# scheamt_projekt.net
KiCad netlist of a schematic drawn in EAGLE
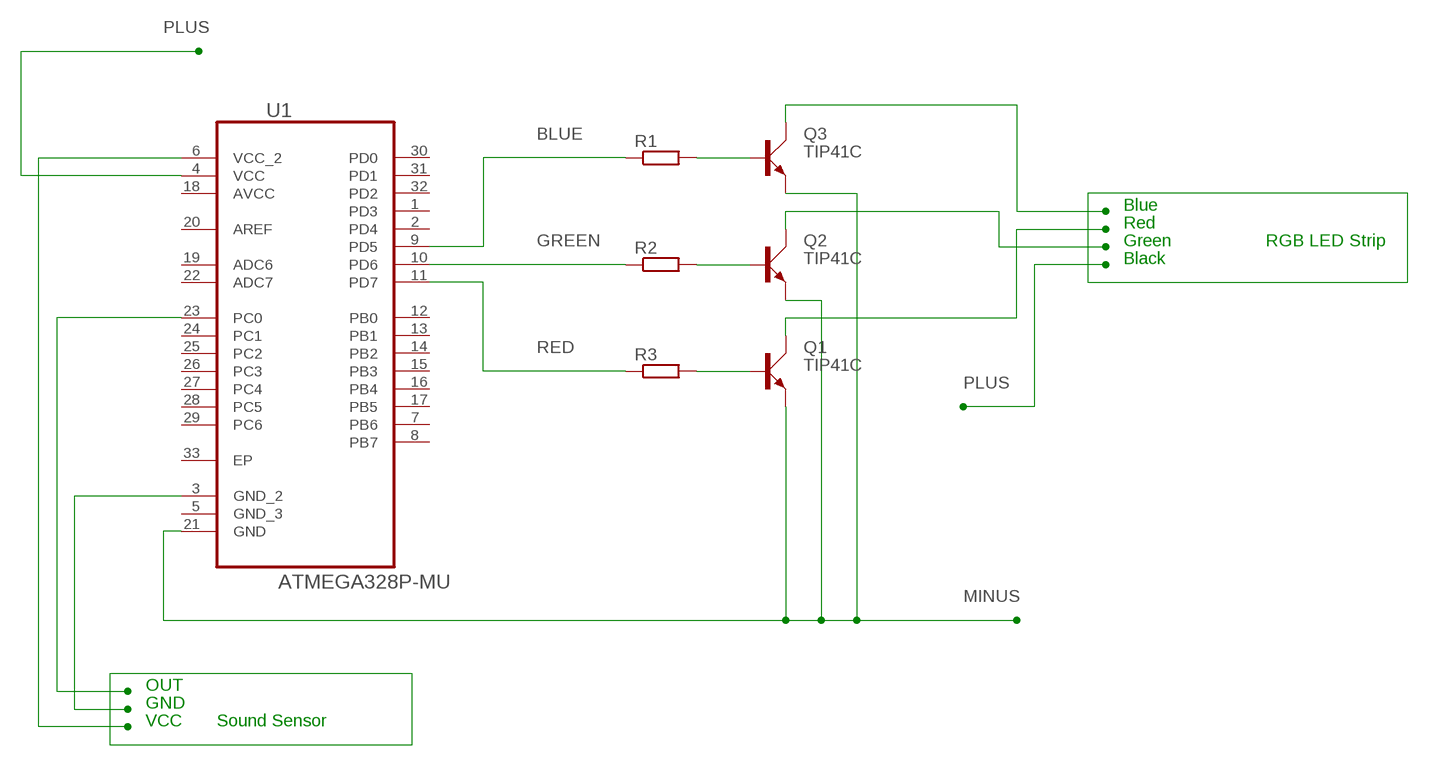
[diagram p0: schematic, sheet 1]

(export (version "E")
  (design (tool "Eeschema 10.0.6"))
  (components
    (comp (ref "Q1")
      (value "TIP41C")
      (footprint "eagle-import:TO220AV")
      (libsource (lib "eagle-import") (part "TIP41C"))
    )
    (comp (ref "Q2")
      (value "TIP41C")
      (footprint "eagle-import:TO220AV")
      (libsource (lib "eagle-import") (part "TIP41C"))
    )
    (comp (ref "Q3")
      (value "TIP41C")
      (footprint "eagle-import:TO220AV")
      (libsource (lib "eagle-import") (part "TIP41C"))
    )
    (comp (ref "R1")
      (value "R-EU_0204/7")
      (footprint "eagle-import:0204_7")
      (libsource (lib "eagle-import") (part "R-EU_0204/7"))
    )
    (comp (ref "R2")
      (value "R-EU_0204/7")
      (footprint "eagle-import:0204_7")
      (libsource (lib "eagle-import") (part "R-EU_0204/7"))
    )
    (comp (ref "R3")
      (value "R-EU_0204/7")
      (footprint "eagle-import:0204_7")
      (libsource (lib "eagle-import") (part "R-EU_0204/7"))
    )
    (comp (ref "U1")
      (value "ATMEGA328P-MU")
      (footprint "eagle-import:QFN50P500X500X100-33N")
      (fields (field (name "SUPPLIER") "Atmel"))
      (libsource (lib "eagle-import") (part "ATMEGA328P-MU"))
    )
  )
  (nets
    (net (code "1") (name "/AVCC") (class "Default")
      (node (ref "U1") (pin "18") (pinfunction "AVCC_18") (pintype "power_in"))
    )
    (net (code "2") (name "/BLUE") (class "Default")
      (node (ref "R1") (pin "1") (pinfunction "1_1") (pintype "passive"))
      (node (ref "U1") (pin "9") (pinfunction "PD5_9") (pintype "bidirectional"))
    )
    (net (code "3") (name "/GREEN") (class "Default")
      (node (ref "R2") (pin "1") (pinfunction "1_1") (pintype "passive"))
      (node (ref "U1") (pin "10") (pinfunction "PD6_10") (pintype "bidirectional"))
    )
    (net (code "4") (name "/MINUS") (class "Default")
      (node (ref "Q1") (pin "E") (pinfunction "E_E") (pintype "passive"))
      (node (ref "Q2") (pin "E") (pinfunction "E_E") (pintype "passive"))
      (node (ref "Q3") (pin "E") (pinfunction "E_E") (pintype "passive"))
      (node (ref "U1") (pin "21") (pinfunction "GND_21") (pintype "passive"))
    )
    (net (code "5") (name "/PLUS") (class "Default")
      (node (ref "U1") (pin "4") (pinfunction "VCC_4") (pintype "power_in"))
    )
    (net (code "6") (name "/RED") (class "Default")
      (node (ref "R3") (pin "1") (pinfunction "1_1") (pintype "passive"))
      (node (ref "U1") (pin "11") (pinfunction "PD7_11") (pintype "bidirectional"))
    )
    (net (code "7") (name "Net-(Q1-PadB)") (class "Default")
      (node (ref "Q1") (pin "B") (pinfunction "B_B") (pintype "passive"))
      (node (ref "R3") (pin "2") (pinfunction "2_2") (pintype "passive"))
    )
    (net (code "8") (name "Net-(Q2-PadB)") (class "Default")
      (node (ref "Q2") (pin "B") (pinfunction "B_B") (pintype "passive"))
      (node (ref "R2") (pin "2") (pinfunction "2_2") (pintype "passive"))
    )
    (net (code "9") (name "Net-(Q3-PadB)") (class "Default")
      (node (ref "Q3") (pin "B") (pinfunction "B_B") (pintype "passive"))
      (node (ref "R1") (pin "2") (pinfunction "2_2") (pintype "passive"))
    )
    (net (code "10") (name "unconnected-(Q1-PadC)") (class "Default")
      (node (ref "Q1") (pin "C") (pinfunction "C_C") (pintype "passive"))
    )
    (net (code "11") (name "unconnected-(Q2-PadC)") (class "Default")
      (node (ref "Q2") (pin "C") (pinfunction "C_C") (pintype "passive"))
    )
    (net (code "12") (name "unconnected-(Q3-PadC)") (class "Default")
      (node (ref "Q3") (pin "C") (pinfunction "C_C") (pintype "passive"))
    )
    (net (code "13") (name "unconnected-(U1-ADC6-Pad19)") (class "Default")
      (node (ref "U1") (pin "19") (pinfunction "ADC6_19") (pintype "input"))
    )
    (net (code "14") (name "unconnected-(U1-ADC7-Pad22)") (class "Default")
      (node (ref "U1") (pin "22") (pinfunction "ADC7_22") (pintype "input"))
    )
    (net (code "15") (name "unconnected-(U1-AREF-Pad20)") (class "Default")
      (node (ref "U1") (pin "20") (pinfunction "AREF_20") (pintype "input"))
    )
    (net (code "16") (name "unconnected-(U1-EP-Pad33)") (class "Default")
      (node (ref "U1") (pin "33") (pinfunction "EP_33") (pintype "passive"))
    )
    (net (code "17") (name "unconnected-(U1-GND_2-Pad3)") (class "Default")
      (node (ref "U1") (pin "3") (pinfunction "GND_2_3") (pintype "passive"))
    )
    (net (code "18") (name "unconnected-(U1-GND_3-Pad5)") (class "Default")
      (node (ref "U1") (pin "5") (pinfunction "GND_3_5") (pintype "passive"))
    )
    (net (code "19") (name "unconnected-(U1-PB0-Pad12)") (class "Default")
      (node (ref "U1") (pin "12") (pinfunction "PB0_12") (pintype "bidirectional"))
    )
    (net (code "20") (name "unconnected-(U1-PB1-Pad13)") (class "Default")
      (node (ref "U1") (pin "13") (pinfunction "PB1_13") (pintype "bidirectional"))
    )
    (net (code "21") (name "unconnected-(U1-PB2-Pad14)") (class "Default")
      (node (ref "U1") (pin "14") (pinfunction "PB2_14") (pintype "bidirectional"))
    )
    (net (code "22") (name "unconnected-(U1-PB3-Pad15)") (class "Default")
      (node (ref "U1") (pin "15") (pinfunction "PB3_15") (pintype "bidirectional"))
    )
    (net (code "23") (name "unconnected-(U1-PB4-Pad16)") (class "Default")
      (node (ref "U1") (pin "16") (pinfunction "PB4_16") (pintype "bidirectional"))
    )
    (net (code "24") (name "unconnected-(U1-PB5-Pad17)") (class "Default")
      (node (ref "U1") (pin "17") (pinfunction "PB5_17") (pintype "bidirectional"))
    )
    (net (code "25") (name "unconnected-(U1-PB6-Pad7)") (class "Default")
      (node (ref "U1") (pin "7") (pinfunction "PB6_7") (pintype "bidirectional"))
    )
    (net (code "26") (name "unconnected-(U1-PB7-Pad8)") (class "Default")
      (node (ref "U1") (pin "8") (pinfunction "PB7_8") (pintype "bidirectional"))
    )
    (net (code "27") (name "unconnected-(U1-PC0-Pad23)") (class "Default")
      (node (ref "U1") (pin "23") (pinfunction "PC0_23") (pintype "bidirectional"))
    )
    (net (code "28") (name "unconnected-(U1-PC1-Pad24)") (class "Default")
      (node (ref "U1") (pin "24") (pinfunction "PC1_24") (pintype "bidirectional"))
    )
    (net (code "29") (name "unconnected-(U1-PC2-Pad25)") (class "Default")
      (node (ref "U1") (pin "25") (pinfunction "PC2_25") (pintype "bidirectional"))
    )
    (net (code "30") (name "unconnected-(U1-PC3-Pad26)") (class "Default")
      (node (ref "U1") (pin "26") (pinfunction "PC3_26") (pintype "bidirectional"))
    )
    (net (code "31") (name "unconnected-(U1-PC4-Pad27)") (class "Default")
      (node (ref "U1") (pin "27") (pinfunction "PC4_27") (pintype "bidirectional"))
    )
    (net (code "32") (name "unconnected-(U1-PC5-Pad28)") (class "Default")
      (node (ref "U1") (pin "28") (pinfunction "PC5_28") (pintype "bidirectional"))
    )
    (net (code "33") (name "unconnected-(U1-PC6-Pad29)") (class "Default")
      (node (ref "U1") (pin "29") (pinfunction "PC6_29") (pintype "bidirectional"))
    )
    (net (code "34") (name "unconnected-(U1-PD0-Pad30)") (class "Default")
      (node (ref "U1") (pin "30") (pinfunction "PD0_30") (pintype "bidirectional"))
    )
    (net (code "35") (name "unconnected-(U1-PD1-Pad31)") (class "Default")
      (node (ref "U1") (pin "31") (pinfunction "PD1_31") (pintype "bidirectional"))
    )
    (net (code "36") (name "unconnected-(U1-PD2-Pad32)") (class "Default")
      (node (ref "U1") (pin "32") (pinfunction "PD2_32") (pintype "bidirectional"))
    )
    (net (code "37") (name "unconnected-(U1-PD3-Pad1)") (class "Default")
      (node (ref "U1") (pin "1") (pinfunction "PD3_1") (pintype "bidirectional"))
    )
    (net (code "38") (name "unconnected-(U1-PD4-Pad2)") (class "Default")
      (node (ref "U1") (pin "2") (pinfunction "PD4_2") (pintype "bidirectional"))
    )
    (net (code "39") (name "unconnected-(U1-VCC_2-Pad6)") (class "Default")
      (node (ref "U1") (pin "6") (pinfunction "VCC_2_6") (pintype "power_in"))
    )
  )
)
